# IMU.net
KiCad netlist of a schematic drawn in Altium Designer
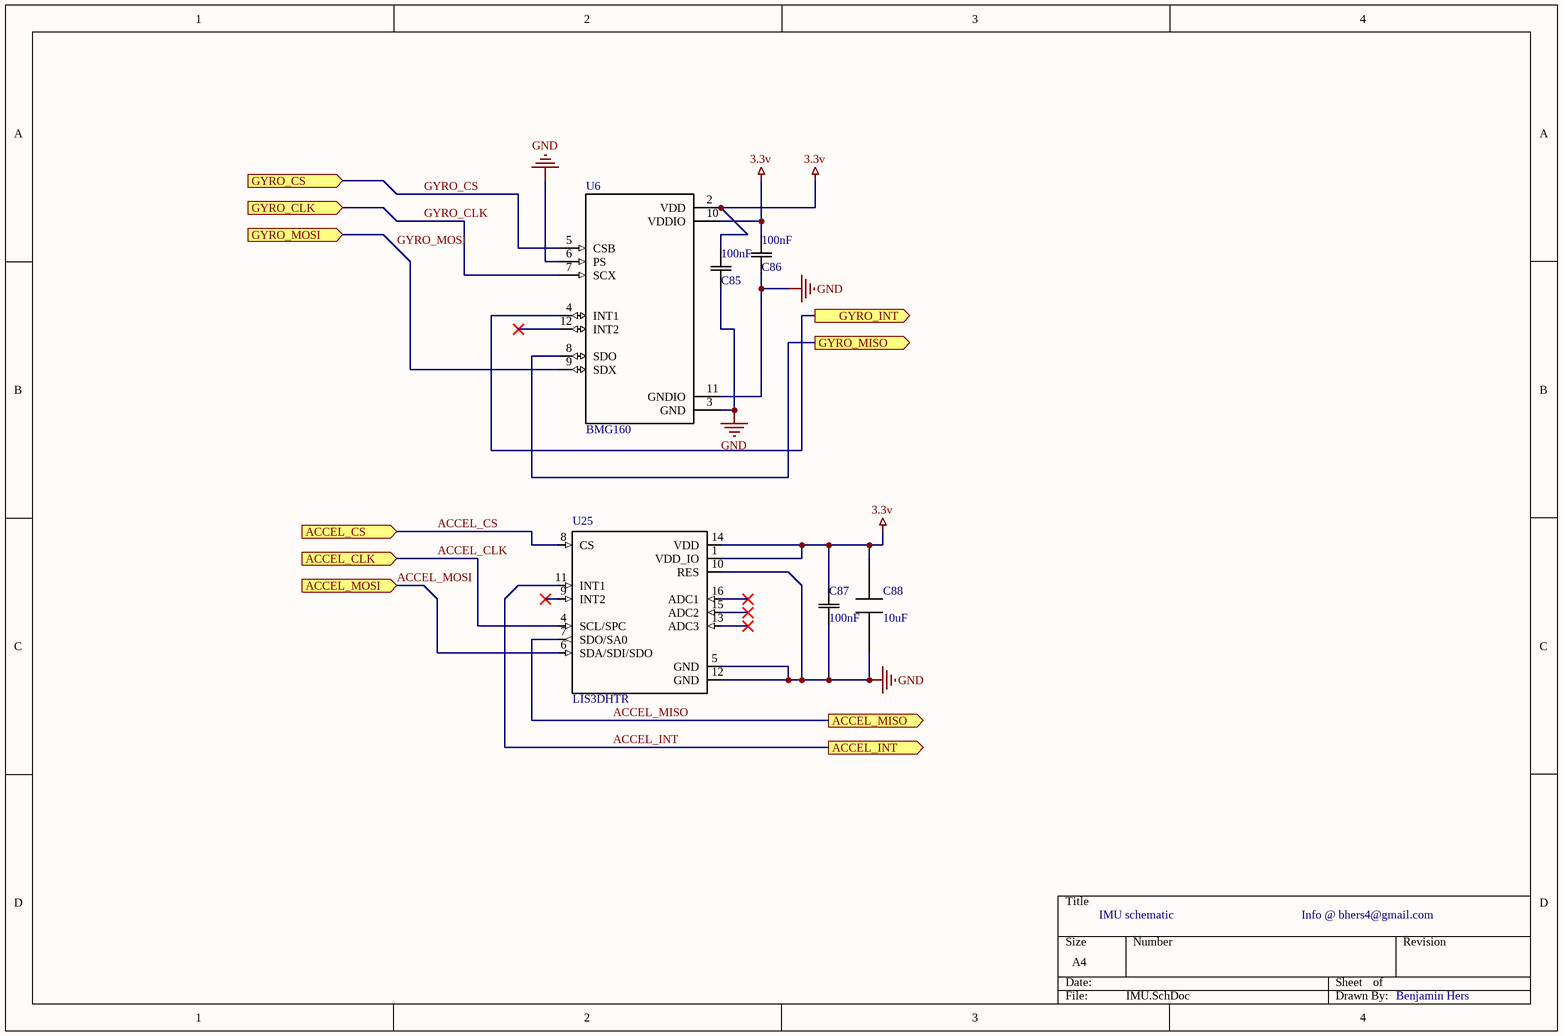
[diagram p0: IMU.SchDoc]

(export (version "E")
  (design (tool "Eeschema 10.0.6"))
  (components
    (comp (ref "C85")
      (value "100nF")
      (footprint "CAPC2013X110N")
      (description "Capacitor; Ceramic; Cap; .100UF ; Tol+-10%; SMD; Vol-Rtg 50V; X7R, Tape/Reel")
      (fields (field (name "MP") "C0805C104K5RACTU") (field (name "MF") "Kemet"))
      (libsource (lib "100nF-C0805C104K5RACTU") (part "C0805C104K5RACTU"))
    )
    (comp (ref "C86")
      (value "100nF")
      (footprint "CAPC2013X110N")
      (description "Capacitor; Ceramic; Cap; .100UF ; Tol+-10%; SMD; Vol-Rtg 50V; X7R, Tape/Reel")
      (fields (field (name "MP") "C0805C104K5RACTU") (field (name "MF") "Kemet"))
      (libsource (lib "100nF-C0805C104K5RACTU") (part "C0805C104K5RACTU"))
    )
    (comp (ref "C87")
      (value "100nF")
      (footprint "CAPC2013X110N")
      (description "Capacitor; Ceramic; Cap; .100UF ; Tol+-10%; SMD; Vol-Rtg 50V; X7R, Tape/Reel")
      (fields (field (name "MP") "C0805C104K5RACTU") (field (name "MF") "Kemet"))
      (libsource (lib "") (part "C0805C104K5RACTU_1"))
    )
    (comp (ref "C88")
      (value "10uF")
      (footprint "CAPC3216X100N")
      (libsource (lib "10uFCAPC3216X100N") (part "Component_1"))
    )
    (comp (ref "U6")
      (value "BMG160")
      (footprint "OFN50P300X300X100-12N")
      (description "BMG160 Series 16 Bit 2000Â°/s 3-Axis Angular Rate Gyroscope Sensor 3 mm x 3 mm")
      (fields (field (name "DIGI-KEY_PART_NUMBER") "828-1042-1-ND") (field (name "MF") "Bosch"))
      (libsource (lib "BoschGryoBMG160") (part "BMG160"))
    )
    (comp (ref "U25")
      (value "LIS3DHTR")
      (footprint "LGA16R50P5X3_300X300X100N")
      (description "MEMS digital output motion sensor ultra low-power high performance 3-axes")
      (fields (field (name "MF") "STMicroelectronics"))
      (libsource (lib "LIS3DHTR") (part "LIS3DHTR"))
    )
  )
  (nets
    (net (code "1") (name "/ACCEL_CLK") (class "Default")
      (node (ref "U25") (pin "4") (pinfunction "SCL/SPC_4") (pintype "input"))
    )
    (net (code "2") (name "/ACCEL_CS") (class "Default")
      (node (ref "U25") (pin "8") (pinfunction "CS_8") (pintype "input"))
    )
    (net (code "3") (name "/ACCEL_INT") (class "Default")
      (node (ref "U25") (pin "11") (pinfunction "INT1_11") (pintype "input"))
    )
    (net (code "4") (name "/ACCEL_MISO") (class "Default")
      (node (ref "U25") (pin "7") (pinfunction "SDO/SA0_7") (pintype "output"))
    )
    (net (code "5") (name "/ACCEL_MOSI") (class "Default")
      (node (ref "U25") (pin "6") (pinfunction "SDA/SDI/SDO_6") (pintype "input"))
    )
    (net (code "6") (name "/GYRO_CLK") (class "Default")
      (node (ref "U6") (pin "7") (pinfunction "SCX_7") (pintype "input"))
    )
    (net (code "7") (name "/GYRO_CS") (class "Default")
      (node (ref "U6") (pin "5") (pinfunction "CSB_5") (pintype "input"))
    )
    (net (code "8") (name "/GYRO_INT") (class "Default")
      (node (ref "U6") (pin "4") (pinfunction "INT1_4") (pintype "bidirectional"))
    )
    (net (code "9") (name "/GYRO_MISO") (class "Default")
      (node (ref "U6") (pin "8") (pinfunction "SDO_8") (pintype "bidirectional"))
    )
    (net (code "10") (name "/GYRO_MOSI") (class "Default")
      (node (ref "U6") (pin "9") (pinfunction "SDX_9") (pintype "bidirectional"))
    )
    (net (code "11") (name "3.3v") (class "Default")
      (node (ref "C85") (pin "1") (pinfunction "C1_1") (pintype "passive"))
      (node (ref "C86") (pin "1") (pinfunction "C1_1") (pintype "passive"))
      (node (ref "C87") (pin "2") (pinfunction "C2_2") (pintype "passive"))
      (node (ref "U25") (pin "1") (pinfunction "VDD_IO_1") (pintype "power_in"))
      (node (ref "U25") (pin "14") (pinfunction "VDD_14") (pintype "power_in"))
      (node (ref "U6") (pin "10") (pinfunction "VDDIO_10") (pintype "power_in"))
      (node (ref "U6") (pin "2") (pinfunction "VDD_2") (pintype "power_in"))
    )
    (net (code "12") (name "GND") (class "Default")
      (node (ref "C85") (pin "2") (pinfunction "C2_2") (pintype "passive"))
      (node (ref "C86") (pin "2") (pinfunction "C2_2") (pintype "passive"))
      (node (ref "C87") (pin "1") (pinfunction "C1_1") (pintype "passive"))
      (node (ref "U25") (pin "10") (pinfunction "RES_10") (pintype "power_in"))
      (node (ref "U25") (pin "12") (pinfunction "GND_12") (pintype "power_in"))
      (node (ref "U25") (pin "5") (pinfunction "GND_5") (pintype "power_in"))
      (node (ref "U6") (pin "11") (pinfunction "GNDIO_11") (pintype "passive"))
      (node (ref "U6") (pin "3") (pinfunction "GND_3") (pintype "passive"))
      (node (ref "U6") (pin "6") (pinfunction "PS_6") (pintype "input"))
    )
    (net (code "13") (name "unconnected-(C88-PadIn)") (class "Default")
      (node (ref "C88") (pin "In") (pinfunction "In_In") (pintype "passive"))
    )
    (net (code "14") (name "unconnected-(C88-PadOut)") (class "Default")
      (node (ref "C88") (pin "Out") (pinfunction "Out_Out") (pintype "passive"))
    )
    (net (code "15") (name "unconnected-(U6-INT2-Pad12)") (class "Default")
      (node (ref "U6") (pin "12") (pinfunction "INT2_12") (pintype "bidirectional+no_connect"))
    )
    (net (code "16") (name "unconnected-(U25-ADC1-Pad16)") (class "Default")
      (node (ref "U25") (pin "16") (pinfunction "ADC1_16") (pintype "input+no_connect"))
    )
    (net (code "17") (name "unconnected-(U25-ADC2-Pad15)") (class "Default")
      (node (ref "U25") (pin "15") (pinfunction "ADC2_15") (pintype "input+no_connect"))
    )
    (net (code "18") (name "unconnected-(U25-ADC3-Pad13)") (class "Default")
      (node (ref "U25") (pin "13") (pinfunction "ADC3_13") (pintype "input+no_connect"))
    )
    (net (code "19") (name "unconnected-(U25-INT2-Pad9)") (class "Default")
      (node (ref "U25") (pin "9") (pinfunction "INT2_9") (pintype "input+no_connect"))
    )
  )
)
